# LoRa.net
KiCad netlist of a schematic drawn in Altium Designer
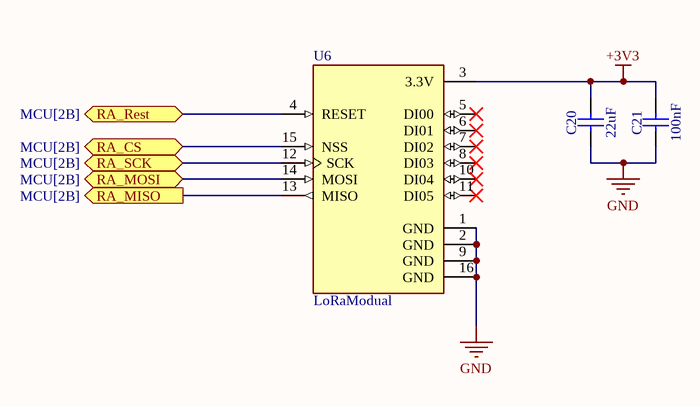
[diagram p0: LoRa.SchDoc]

(export (version "E")
  (design (tool "Eeschema 10.0.6"))
  (components
    (comp (ref "C20")
      (value "22uF")
      (footprint "CAPC1608X90N")
      (description "Non-polarised capacitor")
      (fields
        (field (name "PART NUMBER") "CC0603_22UF_6.3V_20%_X5R")
        (field (name "VOLTAGE") "6.3V")
        (field (name "AUTHOR") "CERN DEM JLC")
      )
      (libsource (lib "Capacitors") (part "Capacitor - non polarized"))
    )
    (comp (ref "C21")
      (value "100nF")
      (footprint "CAPC1608X90N")
      (description "Non-polarised capacitor")
      (fields
        (field (name "PART NUMBER") "CC0603_100NF_100V_10%_X7R")
        (field (name "VOLTAGE") "100V")
        (field (name "AUTHOR") "CERN DEM JLC")
      )
      (libsource (lib "Capacitors") (part "Capacitor - non polarized"))
    )
    (comp (ref "U6")
      (value "LoRaModual")
      (footprint "IC.RA-02")
      (fields (field (name "MF") "Ai-Thinker") (field (name "MP") "RA-02"))
      (libsource (lib "ParsaAltiumSCHLIB") (part "IC.RA-02"))
    )
  )
  (nets
    (net (code "1") (name "+3V3") (class "Default")
      (node (ref "C20") (pin "2") (pinfunction "2_2") (pintype "passive"))
      (node (ref "C21") (pin "2") (pinfunction "2_2") (pintype "passive"))
      (node (ref "U6") (pin "3") (pinfunction "3.3V_3") (pintype "power_in"))
    )
    (net (code "2") (name "/RA_CS") (class "Default")
      (node (ref "U6") (pin "15") (pinfunction "NSS_15") (pintype "input"))
    )
    (net (code "3") (name "/RA_MISO") (class "Default")
      (node (ref "U6") (pin "13") (pinfunction "MISO_13") (pintype "output"))
    )
    (net (code "4") (name "/RA_MOSI") (class "Default")
      (node (ref "U6") (pin "14") (pinfunction "MOSI_14") (pintype "input"))
    )
    (net (code "5") (name "/RA_Rest") (class "Default")
      (node (ref "U6") (pin "4") (pinfunction "RESET_4") (pintype "input"))
    )
    (net (code "6") (name "/RA_SCK") (class "Default")
      (node (ref "U6") (pin "12") (pinfunction "SCK_12") (pintype "input"))
    )
    (net (code "7") (name "GND") (class "Default")
      (node (ref "C20") (pin "1") (pinfunction "1_1") (pintype "passive"))
      (node (ref "C21") (pin "1") (pinfunction "1_1") (pintype "passive"))
      (node (ref "U6") (pin "1") (pinfunction "GND_1") (pintype "power_in"))
      (node (ref "U6") (pin "16") (pinfunction "GND_16") (pintype "power_in"))
      (node (ref "U6") (pin "2") (pinfunction "GND_2") (pintype "power_in"))
      (node (ref "U6") (pin "9") (pinfunction "GND_9") (pintype "power_in"))
    )
    (net (code "8") (name "unconnected-(U6-DI00-Pad5)") (class "Default")
      (node (ref "U6") (pin "5") (pinfunction "DI00_5") (pintype "bidirectional+no_connect"))
    )
    (net (code "9") (name "unconnected-(U6-DI01-Pad6)") (class "Default")
      (node (ref "U6") (pin "6") (pinfunction "DI01_6") (pintype "bidirectional+no_connect"))
    )
    (net (code "10") (name "unconnected-(U6-DI02-Pad7)") (class "Default")
      (node (ref "U6") (pin "7") (pinfunction "DI02_7") (pintype "bidirectional+no_connect"))
    )
    (net (code "11") (name "unconnected-(U6-DI03-Pad8)") (class "Default")
      (node (ref "U6") (pin "8") (pinfunction "DI03_8") (pintype "bidirectional+no_connect"))
    )
    (net (code "12") (name "unconnected-(U6-DI04-Pad10)") (class "Default")
      (node (ref "U6") (pin "10") (pinfunction "DI04_10") (pintype "bidirectional+no_connect"))
    )
    (net (code "13") (name "unconnected-(U6-DI05-Pad11)") (class "Default")
      (node (ref "U6") (pin "11") (pinfunction "DI05_11") (pintype "bidirectional+no_connect"))
    )
  )
)
